# sirin-clone-schematic.net
KiCad netlist of a schematic drawn in EAGLE
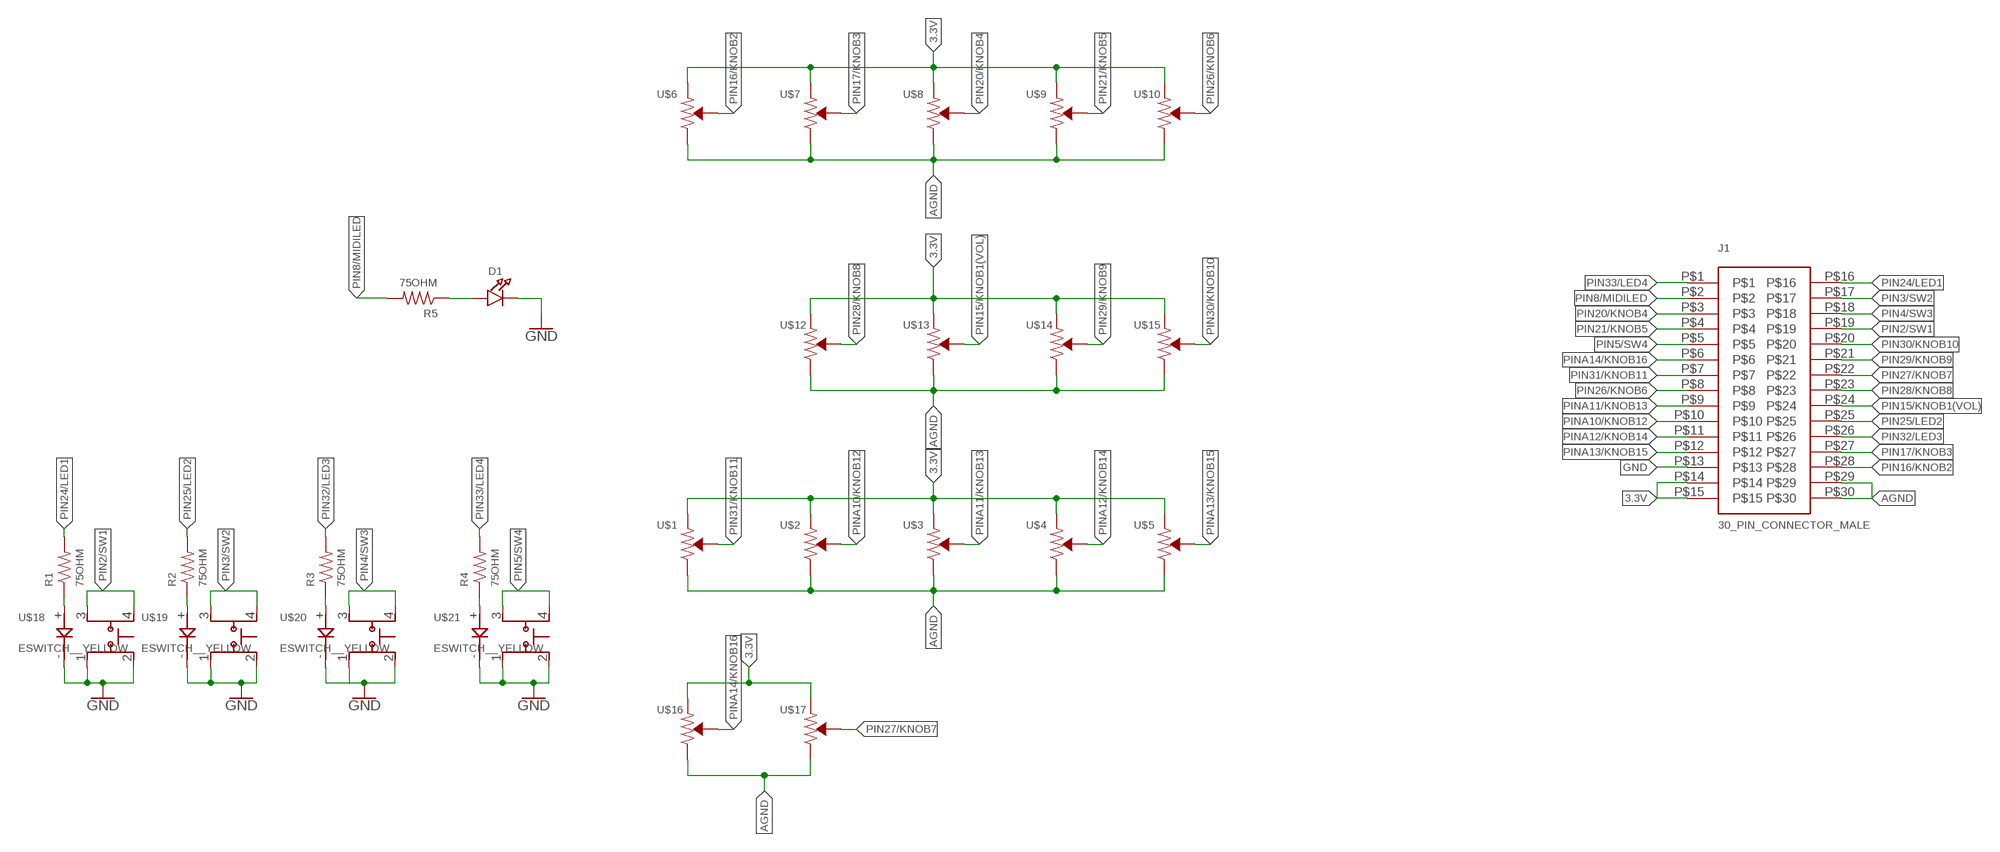
[diagram p0: schematic, sheet 1]

(export (version "E")
  (design (tool "Eeschema 10.0.6"))
  (components
    (comp (ref "D1")
      (value "LED_RED0805")
      (footprint "eagle-import:CHIPLED_0805")
      (fields (field (name "MPN") "150060RS75000"))
      (libsource (lib "eagle-import") (part "LED_RED0805"))
    )
    (comp (ref "J1")
      (value "30_PIN_CONNECTOR_MALE")
      (footprint "eagle-import:MOLEX_30PINCONNECTOR_2MM")
      (fields (field (name "SPICEPREFIX") "X"))
      (libsource (lib "eagle-import") (part "30_PIN_CONNECTOR_MALE"))
    )
    (comp (ref "R1")
      (value "75OHM")
      (footprint "eagle-import:0805")
      (fields (field (name "MPN") "RNCP0805FTD75R0"))
      (libsource (lib "eagle-import") (part "75OHM"))
    )
    (comp (ref "R2")
      (value "75OHM")
      (footprint "eagle-import:0805")
      (fields (field (name "MPN") "RNCP0805FTD75R0"))
      (libsource (lib "eagle-import") (part "75OHM"))
    )
    (comp (ref "R3")
      (value "75OHM")
      (footprint "eagle-import:0805")
      (fields (field (name "MPN") "RNCP0805FTD75R0"))
      (libsource (lib "eagle-import") (part "75OHM"))
    )
    (comp (ref "R4")
      (value "75OHM")
      (footprint "eagle-import:0805")
      (fields (field (name "MPN") "RNCP0805FTD75R0"))
      (libsource (lib "eagle-import") (part "75OHM"))
    )
    (comp (ref "R5")
      (value "75OHM")
      (footprint "eagle-import:0805")
      (fields (field (name "MPN") "RNCP0805FTD75R0"))
      (libsource (lib "eagle-import") (part "75OHM"))
    )
    (comp (ref "U$1")
      (value "BOURNS_10K_POTENTIOMETER")
      (footprint "eagle-import:BOURNS_PTV09")
      (fields (field (name "MPN") "PTV09A-4020F-B103  "))
      (libsource (lib "eagle-import") (part "BOURNS_10K_POTENTIOMETER"))
    )
    (comp (ref "U$2")
      (value "BOURNS_10K_POTENTIOMETER")
      (footprint "eagle-import:BOURNS_PTV09")
      (fields (field (name "MPN") "PTV09A-4020F-B103  "))
      (libsource (lib "eagle-import") (part "BOURNS_10K_POTENTIOMETER"))
    )
    (comp (ref "U$3")
      (value "BOURNS_10K_POTENTIOMETER")
      (footprint "eagle-import:BOURNS_PTV09")
      (fields (field (name "MPN") "PTV09A-4020F-B103  "))
      (libsource (lib "eagle-import") (part "BOURNS_10K_POTENTIOMETER"))
    )
    (comp (ref "U$4")
      (value "BOURNS_10K_POTENTIOMETER")
      (footprint "eagle-import:BOURNS_PTV09")
      (fields (field (name "MPN") "PTV09A-4020F-B103  "))
      (libsource (lib "eagle-import") (part "BOURNS_10K_POTENTIOMETER"))
    )
    (comp (ref "U$5")
      (value "BOURNS_10K_POTENTIOMETER")
      (footprint "eagle-import:BOURNS_PTV09")
      (fields (field (name "MPN") "PTV09A-4020F-B103  "))
      (libsource (lib "eagle-import") (part "BOURNS_10K_POTENTIOMETER"))
    )
    (comp (ref "U$6")
      (value "BOURNS_10K_POTENTIOMETER")
      (footprint "eagle-import:BOURNS_PTV09")
      (fields (field (name "MPN") "PTV09A-4020F-B103  "))
      (libsource (lib "eagle-import") (part "BOURNS_10K_POTENTIOMETER"))
    )
    (comp (ref "U$7")
      (value "BOURNS_10K_POTENTIOMETER")
      (footprint "eagle-import:BOURNS_PTV09")
      (fields (field (name "MPN") "PTV09A-4020F-B103  "))
      (libsource (lib "eagle-import") (part "BOURNS_10K_POTENTIOMETER"))
    )
    (comp (ref "U$8")
      (value "BOURNS_10K_POTENTIOMETER")
      (footprint "eagle-import:BOURNS_PTV09")
      (fields (field (name "MPN") "PTV09A-4020F-B103  "))
      (libsource (lib "eagle-import") (part "BOURNS_10K_POTENTIOMETER"))
    )
    (comp (ref "U$9")
      (value "BOURNS_10K_POTENTIOMETER")
      (footprint "eagle-import:BOURNS_PTV09")
      (fields (field (name "MPN") "PTV09A-4020F-B103  "))
      (libsource (lib "eagle-import") (part "BOURNS_10K_POTENTIOMETER"))
    )
    (comp (ref "U$10")
      (value "BOURNS_10K_POTENTIOMETER")
      (footprint "eagle-import:BOURNS_PTV09")
      (fields (field (name "MPN") "PTV09A-4020F-B103  "))
      (libsource (lib "eagle-import") (part "BOURNS_10K_POTENTIOMETER"))
    )
    (comp (ref "U$12")
      (value "BOURNS_10K_POTENTIOMETER")
      (footprint "eagle-import:BOURNS_PTV09")
      (fields (field (name "MPN") "PTV09A-4020F-B103  "))
      (libsource (lib "eagle-import") (part "BOURNS_10K_POTENTIOMETER"))
    )
    (comp (ref "U$13")
      (value "BOURNS_10K_POTENTIOMETER")
      (footprint "eagle-import:BOURNS_PTV09")
      (fields (field (name "MPN") "PTV09A-4020F-B103  "))
      (libsource (lib "eagle-import") (part "BOURNS_10K_POTENTIOMETER"))
    )
    (comp (ref "U$14")
      (value "BOURNS_10K_POTENTIOMETER")
      (footprint "eagle-import:BOURNS_PTV09")
      (fields (field (name "MPN") "PTV09A-4020F-B103  "))
      (libsource (lib "eagle-import") (part "BOURNS_10K_POTENTIOMETER"))
    )
    (comp (ref "U$15")
      (value "BOURNS_10K_POTENTIOMETER")
      (footprint "eagle-import:BOURNS_PTV09")
      (fields (field (name "MPN") "PTV09A-4020F-B103  "))
      (libsource (lib "eagle-import") (part "BOURNS_10K_POTENTIOMETER"))
    )
    (comp (ref "U$16")
      (value "BOURNS_10K_POTENTIOMETER")
      (footprint "eagle-import:BOURNS_PTV09")
      (fields (field (name "MPN") "PTV09A-4020F-B103  "))
      (libsource (lib "eagle-import") (part "BOURNS_10K_POTENTIOMETER"))
    )
    (comp (ref "U$17")
      (value "BOURNS_10K_POTENTIOMETER")
      (footprint "eagle-import:BOURNS_PTV09")
      (fields (field (name "MPN") "PTV09A-4020F-B103  "))
      (libsource (lib "eagle-import") (part "BOURNS_10K_POTENTIOMETER"))
    )
    (comp (ref "U$18")
      (value "ESWITCH__YELLOW")
      (footprint "eagle-import:ESWITCH_TL1240YQ1JCLR")
      (fields (field (name "MPN") "TL1240YQ1JCLR"))
      (libsource (lib "eagle-import") (part "ESWITCH__YELLOW"))
    )
    (comp (ref "U$19")
      (value "ESWITCH__YELLOW")
      (footprint "eagle-import:ESWITCH_TL1240YQ1JCLR")
      (fields (field (name "MPN") "TL1240YQ1JCLR"))
      (libsource (lib "eagle-import") (part "ESWITCH__YELLOW"))
    )
    (comp (ref "U$20")
      (value "ESWITCH__YELLOW")
      (footprint "eagle-import:ESWITCH_TL1240YQ1JCLR")
      (fields (field (name "MPN") "TL1240YQ1JCLR"))
      (libsource (lib "eagle-import") (part "ESWITCH__YELLOW"))
    )
    (comp (ref "U$21")
      (value "ESWITCH__YELLOW")
      (footprint "eagle-import:ESWITCH_TL1240YQ1JCLR")
      (fields (field (name "MPN") "TL1240YQ1JCLR"))
      (libsource (lib "eagle-import") (part "ESWITCH__YELLOW"))
    )
  )
  (nets
    (net (code "1") (name "3.3V") (class "Default")
      (node (ref "J1") (pin "P$14") (pinfunction "P$14_P$14") (pintype "bidirectional"))
      (node (ref "J1") (pin "P$15") (pinfunction "P$15_P$15") (pintype "bidirectional"))
      (node (ref "U$1") (pin "1") (pinfunction "1_1") (pintype "passive"))
      (node (ref "U$10") (pin "1") (pinfunction "1_1") (pintype "passive"))
      (node (ref "U$12") (pin "1") (pinfunction "1_1") (pintype "passive"))
      (node (ref "U$13") (pin "1") (pinfunction "1_1") (pintype "passive"))
      (node (ref "U$14") (pin "1") (pinfunction "1_1") (pintype "passive"))
      (node (ref "U$15") (pin "1") (pinfunction "1_1") (pintype "passive"))
      (node (ref "U$16") (pin "1") (pinfunction "1_1") (pintype "passive"))
      (node (ref "U$17") (pin "1") (pinfunction "1_1") (pintype "passive"))
      (node (ref "U$2") (pin "1") (pinfunction "1_1") (pintype "passive"))
      (node (ref "U$3") (pin "1") (pinfunction "1_1") (pintype "passive"))
      (node (ref "U$4") (pin "1") (pinfunction "1_1") (pintype "passive"))
      (node (ref "U$5") (pin "1") (pinfunction "1_1") (pintype "passive"))
      (node (ref "U$6") (pin "1") (pinfunction "1_1") (pintype "passive"))
      (node (ref "U$7") (pin "1") (pinfunction "1_1") (pintype "passive"))
      (node (ref "U$8") (pin "1") (pinfunction "1_1") (pintype "passive"))
      (node (ref "U$9") (pin "1") (pinfunction "1_1") (pintype "passive"))
    )
    (net (code "2") (name "AGND") (class "Default")
      (node (ref "J1") (pin "P$29") (pinfunction "P$29_P$29") (pintype "bidirectional"))
      (node (ref "J1") (pin "P$30") (pinfunction "P$30_P$30") (pintype "bidirectional"))
      (node (ref "U$1") (pin "3") (pinfunction "3_3") (pintype "passive"))
      (node (ref "U$10") (pin "3") (pinfunction "3_3") (pintype "passive"))
      (node (ref "U$12") (pin "3") (pinfunction "3_3") (pintype "passive"))
      (node (ref "U$13") (pin "3") (pinfunction "3_3") (pintype "passive"))
      (node (ref "U$14") (pin "3") (pinfunction "3_3") (pintype "passive"))
      (node (ref "U$15") (pin "3") (pinfunction "3_3") (pintype "passive"))
      (node (ref "U$16") (pin "3") (pinfunction "3_3") (pintype "passive"))
      (node (ref "U$17") (pin "3") (pinfunction "3_3") (pintype "passive"))
      (node (ref "U$2") (pin "3") (pinfunction "3_3") (pintype "passive"))
      (node (ref "U$3") (pin "3") (pinfunction "3_3") (pintype "passive"))
      (node (ref "U$4") (pin "3") (pinfunction "3_3") (pintype "passive"))
      (node (ref "U$5") (pin "3") (pinfunction "3_3") (pintype "passive"))
      (node (ref "U$6") (pin "3") (pinfunction "3_3") (pintype "passive"))
      (node (ref "U$7") (pin "3") (pinfunction "3_3") (pintype "passive"))
      (node (ref "U$8") (pin "3") (pinfunction "3_3") (pintype "passive"))
      (node (ref "U$9") (pin "3") (pinfunction "3_3") (pintype "passive"))
    )
    (net (code "3") (name "GND") (class "Default")
      (node (ref "D1") (pin "C") (pinfunction "C_C") (pintype "passive"))
      (node (ref "J1") (pin "P$13") (pinfunction "P$13_P$13") (pintype "bidirectional"))
      (node (ref "U$18") (pin "-") (pinfunction "-_-") (pintype "bidirectional"))
      (node (ref "U$18") (pin "1") (pinfunction "1_1") (pintype "bidirectional"))
      (node (ref "U$18") (pin "2") (pinfunction "2_2") (pintype "bidirectional"))
      (node (ref "U$19") (pin "-") (pinfunction "-_-") (pintype "bidirectional"))
      (node (ref "U$19") (pin "1") (pinfunction "1_1") (pintype "bidirectional"))
      (node (ref "U$19") (pin "2") (pinfunction "2_2") (pintype "bidirectional"))
      (node (ref "U$20") (pin "-") (pinfunction "-_-") (pintype "bidirectional"))
      (node (ref "U$20") (pin "1") (pinfunction "1_1") (pintype "bidirectional"))
      (node (ref "U$20") (pin "2") (pinfunction "2_2") (pintype "bidirectional"))
      (node (ref "U$21") (pin "-") (pinfunction "-_-") (pintype "bidirectional"))
      (node (ref "U$21") (pin "1") (pinfunction "1_1") (pintype "bidirectional"))
      (node (ref "U$21") (pin "2") (pinfunction "2_2") (pintype "bidirectional"))
    )
    (net (code "4") (name "Net-(D1-PadA)") (class "Default")
      (node (ref "D1") (pin "A") (pinfunction "A_A") (pintype "passive"))
      (node (ref "R5") (pin "1") (pinfunction "1_1") (pintype "passive"))
    )
    (net (code "5") (name "Net-(R1-Pad1)") (class "Default")
      (node (ref "R1") (pin "1") (pinfunction "1_1") (pintype "passive"))
      (node (ref "U$18") (pin "+") (pinfunction "+_+") (pintype "bidirectional"))
    )
    (net (code "6") (name "Net-(R2-Pad1)") (class "Default")
      (node (ref "R2") (pin "1") (pinfunction "1_1") (pintype "passive"))
      (node (ref "U$19") (pin "+") (pinfunction "+_+") (pintype "bidirectional"))
    )
    (net (code "7") (name "Net-(R3-Pad1)") (class "Default")
      (node (ref "R3") (pin "1") (pinfunction "1_1") (pintype "passive"))
      (node (ref "U$20") (pin "+") (pinfunction "+_+") (pintype "bidirectional"))
    )
    (net (code "8") (name "Net-(R4-Pad1)") (class "Default")
      (node (ref "R4") (pin "1") (pinfunction "1_1") (pintype "passive"))
      (node (ref "U$21") (pin "+") (pinfunction "+_+") (pintype "bidirectional"))
    )
    (net (code "9") (name "PIN2{slash}SW1") (class "Default")
      (node (ref "J1") (pin "P$19") (pinfunction "P$19_P$19") (pintype "bidirectional"))
      (node (ref "U$18") (pin "3") (pinfunction "3_3") (pintype "bidirectional"))
      (node (ref "U$18") (pin "4") (pinfunction "4_4") (pintype "bidirectional"))
    )
    (net (code "10") (name "PIN3{slash}SW2") (class "Default")
      (node (ref "J1") (pin "P$17") (pinfunction "P$17_P$17") (pintype "bidirectional"))
      (node (ref "U$19") (pin "3") (pinfunction "3_3") (pintype "bidirectional"))
      (node (ref "U$19") (pin "4") (pinfunction "4_4") (pintype "bidirectional"))
    )
    (net (code "11") (name "PIN4{slash}SW3") (class "Default")
      (node (ref "J1") (pin "P$18") (pinfunction "P$18_P$18") (pintype "bidirectional"))
      (node (ref "U$20") (pin "3") (pinfunction "3_3") (pintype "bidirectional"))
      (node (ref "U$20") (pin "4") (pinfunction "4_4") (pintype "bidirectional"))
    )
    (net (code "12") (name "PIN5{slash}SW4") (class "Default")
      (node (ref "J1") (pin "P$5") (pinfunction "P$5_P$5") (pintype "bidirectional"))
      (node (ref "U$21") (pin "3") (pinfunction "3_3") (pintype "bidirectional"))
      (node (ref "U$21") (pin "4") (pinfunction "4_4") (pintype "bidirectional"))
    )
    (net (code "13") (name "PIN8{slash}MIDILED") (class "Default")
      (node (ref "J1") (pin "P$2") (pinfunction "P$2_P$2") (pintype "bidirectional"))
      (node (ref "R5") (pin "2") (pinfunction "2_2") (pintype "passive"))
    )
    (net (code "14") (name "PIN15{slash}KNOB1(VOL)") (class "Default")
      (node (ref "J1") (pin "P$24") (pinfunction "P$24_P$24") (pintype "bidirectional"))
      (node (ref "U$13") (pin "2") (pinfunction "2_2") (pintype "passive"))
    )
    (net (code "15") (name "PIN16{slash}KNOB2") (class "Default")
      (node (ref "J1") (pin "P$28") (pinfunction "P$28_P$28") (pintype "bidirectional"))
      (node (ref "U$6") (pin "2") (pinfunction "2_2") (pintype "passive"))
    )
    (net (code "16") (name "PIN17{slash}KNOB3") (class "Default")
      (node (ref "J1") (pin "P$27") (pinfunction "P$27_P$27") (pintype "bidirectional"))
      (node (ref "U$7") (pin "2") (pinfunction "2_2") (pintype "passive"))
    )
    (net (code "17") (name "PIN20{slash}KNOB4") (class "Default")
      (node (ref "J1") (pin "P$3") (pinfunction "P$3_P$3") (pintype "bidirectional"))
      (node (ref "U$8") (pin "2") (pinfunction "2_2") (pintype "passive"))
    )
    (net (code "18") (name "PIN21{slash}KNOB5") (class "Default")
      (node (ref "J1") (pin "P$4") (pinfunction "P$4_P$4") (pintype "bidirectional"))
      (node (ref "U$9") (pin "2") (pinfunction "2_2") (pintype "passive"))
    )
    (net (code "19") (name "PIN24{slash}LED1") (class "Default")
      (node (ref "J1") (pin "P$16") (pinfunction "P$16_P$16") (pintype "bidirectional"))
      (node (ref "R1") (pin "2") (pinfunction "2_2") (pintype "passive"))
    )
    (net (code "20") (name "PIN25{slash}LED2") (class "Default")
      (node (ref "J1") (pin "P$25") (pinfunction "P$25_P$25") (pintype "bidirectional"))
      (node (ref "R2") (pin "2") (pinfunction "2_2") (pintype "passive"))
    )
    (net (code "21") (name "PIN26{slash}KNOB6") (class "Default")
      (node (ref "J1") (pin "P$8") (pinfunction "P$8_P$8") (pintype "bidirectional"))
      (node (ref "U$10") (pin "2") (pinfunction "2_2") (pintype "passive"))
    )
    (net (code "22") (name "PIN27{slash}KNOB7") (class "Default")
      (node (ref "J1") (pin "P$22") (pinfunction "P$22_P$22") (pintype "bidirectional"))
      (node (ref "U$17") (pin "2") (pinfunction "2_2") (pintype "passive"))
    )
    (net (code "23") (name "PIN28{slash}KNOB8") (class "Default")
      (node (ref "J1") (pin "P$23") (pinfunction "P$23_P$23") (pintype "bidirectional"))
      (node (ref "U$12") (pin "2") (pinfunction "2_2") (pintype "passive"))
    )
    (net (code "24") (name "PIN29{slash}KNOB9") (class "Default")
      (node (ref "J1") (pin "P$21") (pinfunction "P$21_P$21") (pintype "bidirectional"))
      (node (ref "U$14") (pin "2") (pinfunction "2_2") (pintype "passive"))
    )
    (net (code "25") (name "PIN30{slash}KNOB10") (class "Default")
      (node (ref "J1") (pin "P$20") (pinfunction "P$20_P$20") (pintype "bidirectional"))
      (node (ref "U$15") (pin "2") (pinfunction "2_2") (pintype "passive"))
    )
    (net (code "26") (name "PIN31{slash}KNOB11") (class "Default")
      (node (ref "J1") (pin "P$7") (pinfunction "P$7_P$7") (pintype "bidirectional"))
      (node (ref "U$1") (pin "2") (pinfunction "2_2") (pintype "passive"))
    )
    (net (code "27") (name "PIN32{slash}LED3") (class "Default")
      (node (ref "J1") (pin "P$26") (pinfunction "P$26_P$26") (pintype "bidirectional"))
      (node (ref "R3") (pin "2") (pinfunction "2_2") (pintype "passive"))
    )
    (net (code "28") (name "PIN33{slash}LED4") (class "Default")
      (node (ref "J1") (pin "P$1") (pinfunction "P$1_P$1") (pintype "bidirectional"))
      (node (ref "R4") (pin "2") (pinfunction "2_2") (pintype "passive"))
    )
    (net (code "29") (name "PINA10{slash}KNOB12") (class "Default")
      (node (ref "J1") (pin "P$10") (pinfunction "P$10_P$10") (pintype "bidirectional"))
      (node (ref "U$2") (pin "2") (pinfunction "2_2") (pintype "passive"))
    )
    (net (code "30") (name "PINA11{slash}KNOB13") (class "Default")
      (node (ref "J1") (pin "P$9") (pinfunction "P$9_P$9") (pintype "bidirectional"))
      (node (ref "U$3") (pin "2") (pinfunction "2_2") (pintype "passive"))
    )
    (net (code "31") (name "PINA12{slash}KNOB14") (class "Default")
      (node (ref "J1") (pin "P$11") (pinfunction "P$11_P$11") (pintype "bidirectional"))
      (node (ref "U$4") (pin "2") (pinfunction "2_2") (pintype "passive"))
    )
    (net (code "32") (name "PINA13{slash}KNOB15") (class "Default")
      (node (ref "J1") (pin "P$12") (pinfunction "P$12_P$12") (pintype "bidirectional"))
      (node (ref "U$5") (pin "2") (pinfunction "2_2") (pintype "passive"))
    )
    (net (code "33") (name "PINA14{slash}KNOB16") (class "Default")
      (node (ref "J1") (pin "P$6") (pinfunction "P$6_P$6") (pintype "bidirectional"))
      (node (ref "U$16") (pin "2") (pinfunction "2_2") (pintype "passive"))
    )
  )
)
